# P-MT3620RDB-1-0_PMU.net
KiCad netlist of a schematic drawn in Altium Designer
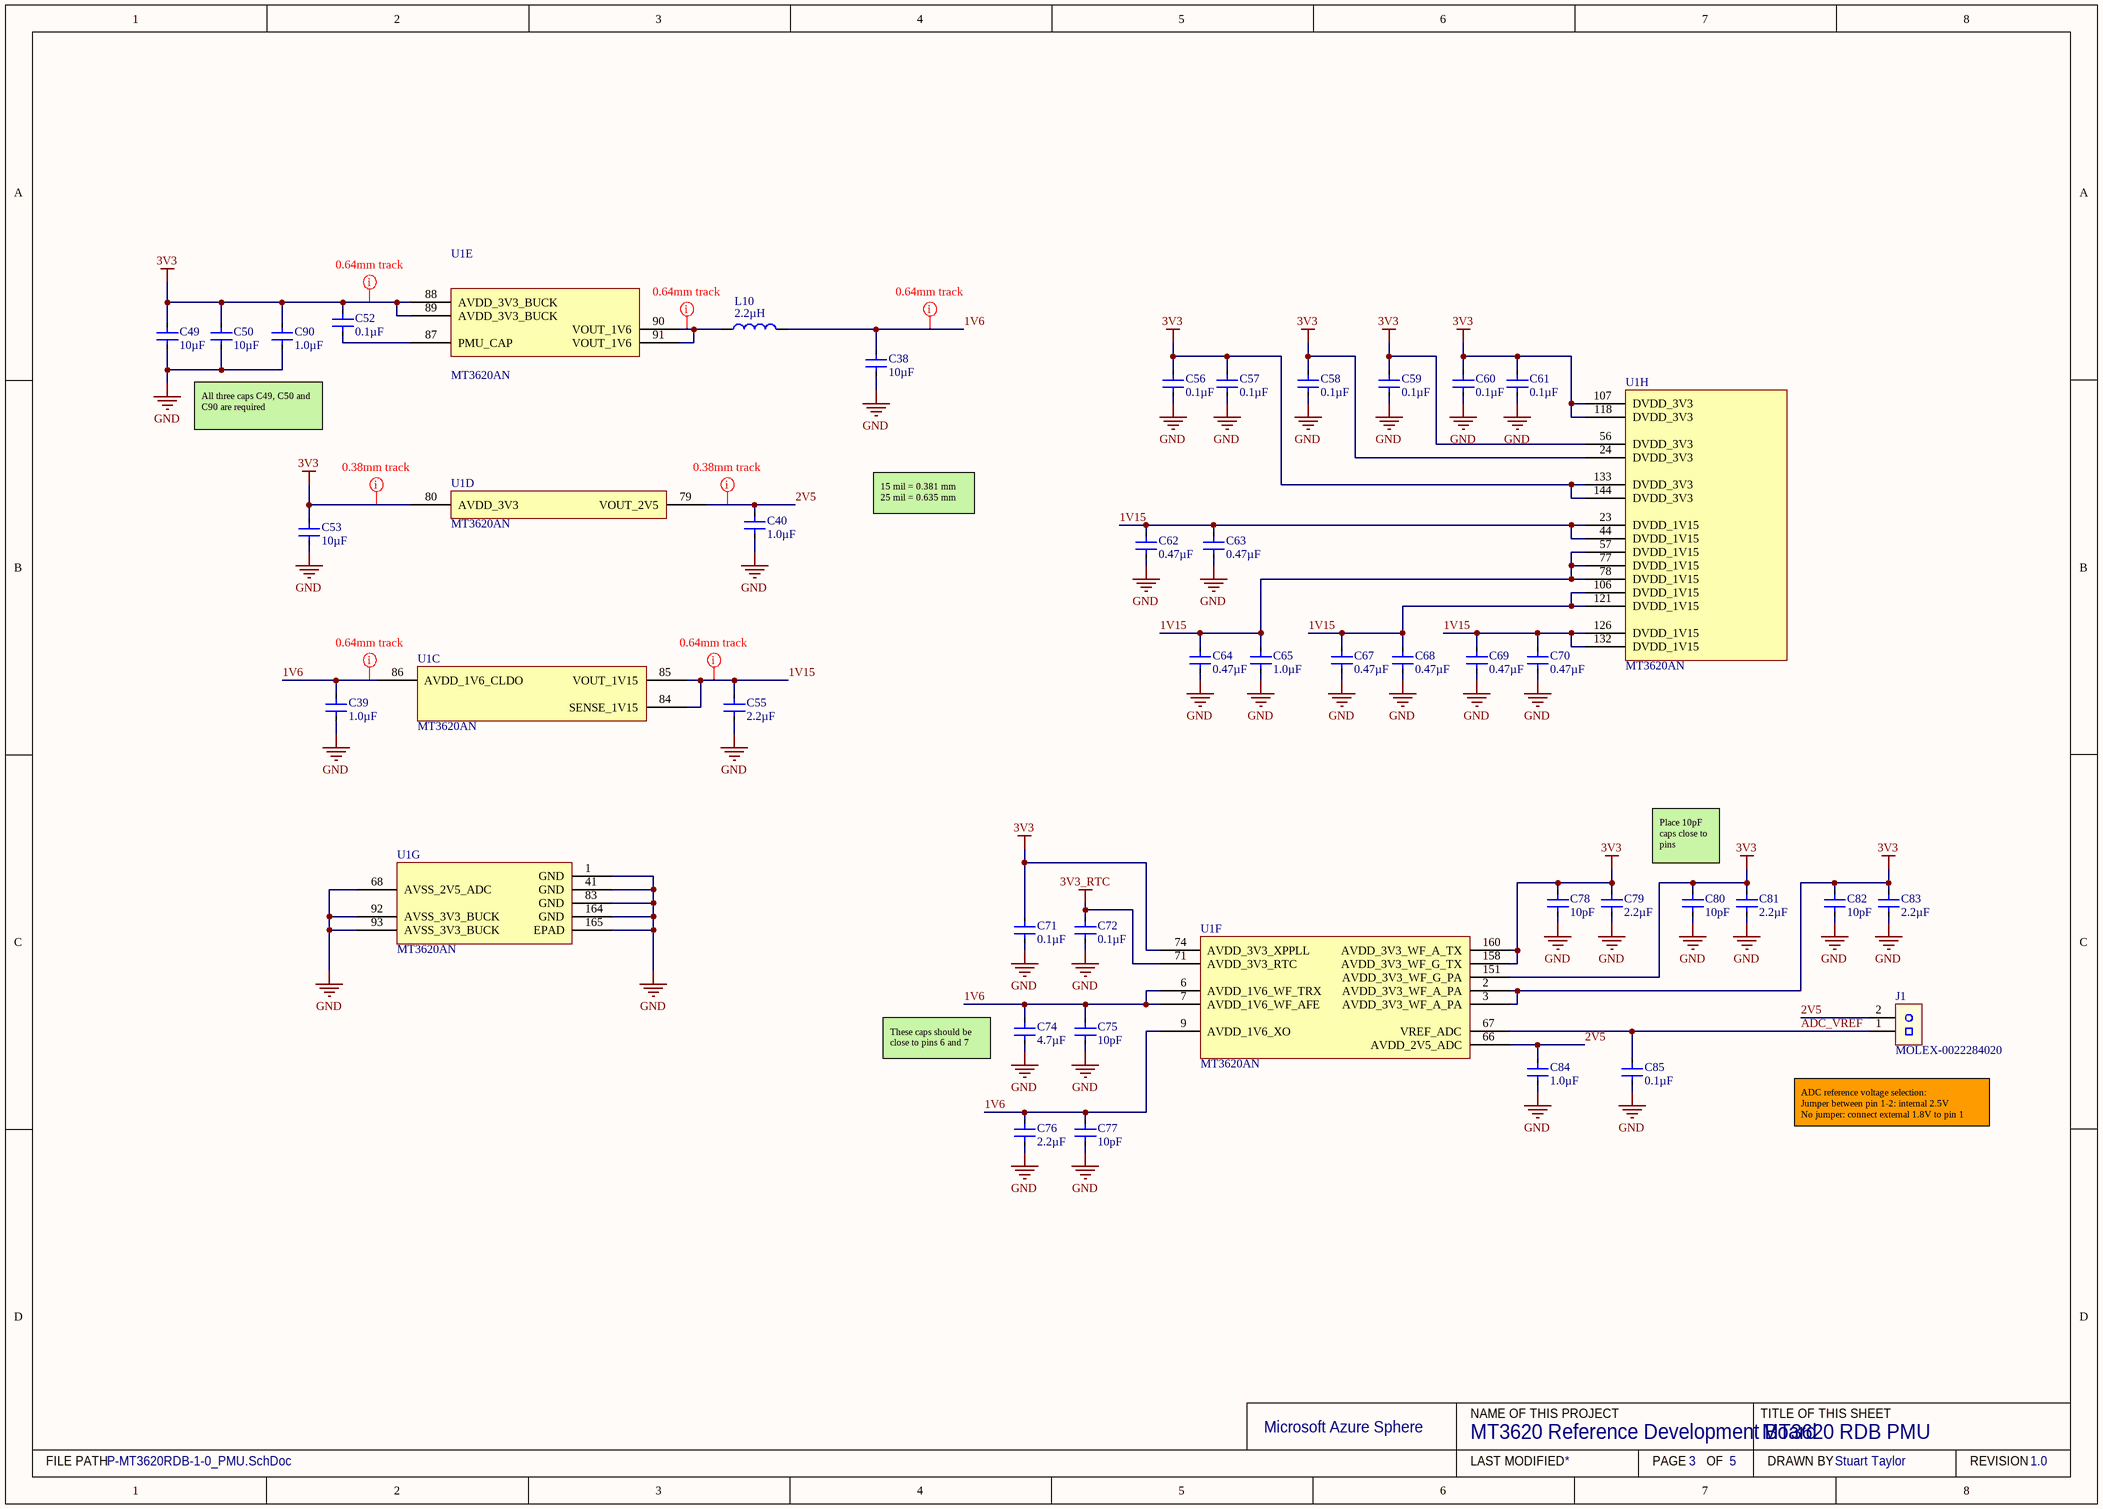
[diagram p0: P-MT3620RDB-1-0_PMU.SchDoc]

(export (version "E")
  (design (tool "Eeschema 10.0.6"))
  (components
    (comp (ref "C38")
      (value "10µF")
      (footprint "CAPC1608-EIA0603-1MM-MED")
      (description "CAP CER 10UF 25V 20% X5R 0603")
      (fields
        (field (name "MANUFACTURER") "TDK Corporation")
        (field (name "MANUFACTURER PART NUMBER") "C1608X5R1E106M080AC")
        (field (name "CAPACITANCE") "10µF")
      )
      (libsource (lib "TDK-Capacitor_C_0603") (part "10µF 0603 X5R 25V"))
    )
    (comp (ref "C39")
      (value "1.0µF")
      (footprint "CAPC1005-EIA0402 0.55MM MED")
      (description "CAP CER 1UF 35V 10% X5R 0402")
      (fields
        (field (name "MANUFACTURER") "TDK Corporation")
        (field (name "MANUFACTURER PART NUMBER") "C1005X5R1V105K050BC")
        (field (name "CAPACITANCE") "1.0µF")
      )
      (libsource (lib "TDK_Capacitor_C_0402") (part "1.0µF 0402 X5R 35V"))
    )
    (comp (ref "C40")
      (value "1.0µF")
      (footprint "CAPC1005-EIA0402 0.55MM MED")
      (description "CAP CER 1UF 35V 10% X5R 0402")
      (fields
        (field (name "MANUFACTURER") "TDK Corporation")
        (field (name "MANUFACTURER PART NUMBER") "C1005X5R1V105K050BC")
        (field (name "CAPACITANCE") "1.0µF")
      )
      (libsource (lib "TDK_Capacitor_C_0402") (part "1.0µF 0402 X5R 35V"))
    )
    (comp (ref "C49")
      (value "10µF")
      (footprint "CAPC1005-EIA0402 0.55MM MED")
      (description "CAP CER 10UF 6.3V 20% X5R 0402")
      (fields
        (field (name "MANUFACTURER") "TDK Corporation")
        (field (name "MANUFACTURER PART NUMBER") "C1005X5R0J106M050BC")
        (field (name "CAPACITANCE") "10µF")
      )
      (libsource (lib "TDK_Capacitor_C_0402") (part "10µF 0402 X5R 6.3V"))
    )
    (comp (ref "C50")
      (value "10µF")
      (footprint "CAPC1005-EIA0402 0.55MM MED")
      (description "CAP CER 10UF 6.3V 20% X5R 0402")
      (fields
        (field (name "MANUFACTURER") "TDK Corporation")
        (field (name "MANUFACTURER PART NUMBER") "C1005X5R0J106M050BC")
        (field (name "CAPACITANCE") "10µF")
      )
      (libsource (lib "TDK_Capacitor_C_0402") (part "10µF 0402 X5R 6.3V"))
    )
    (comp (ref "C52")
      (value "0.1µF")
      (footprint "CAPC1005-EIA0402 0.55MM MED")
      (description "CAP CER 0.1UF 50V 10% X7R 0402")
      (fields
        (field (name "MANUFACTURER") "TDK Corporation")
        (field (name "MANUFACTURER PART NUMBER") "C1005X7R1H104K050BB")
        (field (name "CAPACITANCE") "0.1µF")
      )
      (libsource (lib "TDK_Capacitor_C_0402") (part "0.1µF 0402 X7R 50V"))
    )
    (comp (ref "C53")
      (value "10µF")
      (footprint "CAPC1005-EIA0402 0.55MM MED")
      (description "CAP CER 10UF 6.3V 20% X5R 0402")
      (fields
        (field (name "MANUFACTURER") "TDK Corporation")
        (field (name "MANUFACTURER PART NUMBER") "C1005X5R0J106M050BC")
        (field (name "CAPACITANCE") "10µF")
      )
      (libsource (lib "TDK_Capacitor_C_0402") (part "10µF 0402 X5R 6.3V"))
    )
    (comp (ref "C55")
      (value "2.2µF")
      (footprint "CAPC1005-EIA0402 0.55MM MED")
      (description "CAP CER 2.2UF 35V 10% X5R 0402")
      (fields
        (field (name "MANUFACTURER") "TDK Corporation")
        (field (name "MANUFACTURER PART NUMBER") "C1005X5R1V225K050BC")
        (field (name "CAPACITANCE") "2.2µF")
      )
      (libsource (lib "TDK_Capacitor_C_0402") (part "2.2µF 0402 X5R 35V"))
    )
    (comp (ref "C56")
      (value "0.1µF")
      (footprint "CAPC1005-EIA0402 0.55MM MED")
      (description "CAP CER 0.1UF 50V 10% X7R 0402")
      (fields
        (field (name "MANUFACTURER") "TDK Corporation")
        (field (name "MANUFACTURER PART NUMBER") "C1005X7R1H104K050BB")
        (field (name "CAPACITANCE") "0.1µF")
      )
      (libsource (lib "TDK_Capacitor_C_0402") (part "0.1µF 0402 X7R 50V"))
    )
    (comp (ref "C57")
      (value "0.1µF")
      (footprint "CAPC1005-EIA0402 0.55MM MED")
      (description "CAP CER 0.1UF 50V 10% X7R 0402")
      (fields
        (field (name "MANUFACTURER") "TDK Corporation")
        (field (name "MANUFACTURER PART NUMBER") "C1005X7R1H104K050BB")
        (field (name "CAPACITANCE") "0.1µF")
      )
      (libsource (lib "TDK_Capacitor_C_0402") (part "0.1µF 0402 X7R 50V"))
    )
    (comp (ref "C58")
      (value "0.1µF")
      (footprint "CAPC1005-EIA0402 0.55MM MED")
      (description "CAP CER 0.1UF 50V 10% X7R 0402")
      (fields
        (field (name "MANUFACTURER") "TDK Corporation")
        (field (name "MANUFACTURER PART NUMBER") "C1005X7R1H104K050BB")
        (field (name "CAPACITANCE") "0.1µF")
      )
      (libsource (lib "TDK_Capacitor_C_0402") (part "0.1µF 0402 X7R 50V"))
    )
    (comp (ref "C59")
      (value "0.1µF")
      (footprint "CAPC1005-EIA0402 0.55MM MED")
      (description "CAP CER 0.1UF 50V 10% X7R 0402")
      (fields
        (field (name "MANUFACTURER") "TDK Corporation")
        (field (name "MANUFACTURER PART NUMBER") "C1005X7R1H104K050BB")
        (field (name "CAPACITANCE") "0.1µF")
      )
      (libsource (lib "TDK_Capacitor_C_0402") (part "0.1µF 0402 X7R 50V"))
    )
    (comp (ref "C60")
      (value "0.1µF")
      (footprint "CAPC1005-EIA0402 0.55MM MED")
      (description "CAP CER 0.1UF 50V 10% X7R 0402")
      (fields
        (field (name "MANUFACTURER") "TDK Corporation")
        (field (name "MANUFACTURER PART NUMBER") "C1005X7R1H104K050BB")
        (field (name "CAPACITANCE") "0.1µF")
      )
      (libsource (lib "TDK_Capacitor_C_0402") (part "0.1µF 0402 X7R 50V"))
    )
    (comp (ref "C61")
      (value "0.1µF")
      (footprint "CAPC1005-EIA0402 0.55MM MED")
      (description "CAP CER 0.1UF 50V 10% X7R 0402")
      (fields
        (field (name "MANUFACTURER") "TDK Corporation")
        (field (name "MANUFACTURER PART NUMBER") "C1005X7R1H104K050BB")
        (field (name "CAPACITANCE") "0.1µF")
      )
      (libsource (lib "TDK_Capacitor_C_0402") (part "0.1µF 0402 X7R 50V"))
    )
    (comp (ref "C62")
      (value "0.47µF")
      (footprint "CAPC1005-EIA0402 0.55MM MED")
      (description "CAP CER 0.47UF 35V 10% X5R 0402")
      (fields
        (field (name "MANUFACTURER") "TDK Corporation")
        (field (name "MANUFACTURER PART NUMBER") "C1005X5R1V474K050BC")
        (field (name "CAPACITANCE") "0.47µF")
      )
      (libsource (lib "TDK_Capacitor_C_0402") (part "0.47µF 0402 X5R 35V"))
    )
    (comp (ref "C63")
      (value "0.47µF")
      (footprint "CAPC1005-EIA0402 0.55MM MED")
      (description "CAP CER 0.47UF 35V 10% X5R 0402")
      (fields
        (field (name "MANUFACTURER") "TDK Corporation")
        (field (name "MANUFACTURER PART NUMBER") "C1005X5R1V474K050BC")
        (field (name "CAPACITANCE") "0.47µF")
      )
      (libsource (lib "TDK_Capacitor_C_0402") (part "0.47µF 0402 X5R 35V"))
    )
    (comp (ref "C64")
      (value "0.47µF")
      (footprint "CAPC1005-EIA0402 0.55MM MED")
      (description "CAP CER 0.47UF 35V 10% X5R 0402")
      (fields
        (field (name "MANUFACTURER") "TDK Corporation")
        (field (name "MANUFACTURER PART NUMBER") "C1005X5R1V474K050BC")
        (field (name "CAPACITANCE") "0.47µF")
      )
      (libsource (lib "TDK_Capacitor_C_0402") (part "0.47µF 0402 X5R 35V"))
    )
    (comp (ref "C65")
      (value "1.0µF")
      (footprint "CAPC1005-EIA0402 0.55MM MED")
      (description "CAP CER 1UF 35V 10% X5R 0402")
      (fields
        (field (name "MANUFACTURER") "TDK Corporation")
        (field (name "MANUFACTURER PART NUMBER") "C1005X5R1V105K050BC")
        (field (name "CAPACITANCE") "1.0µF")
      )
      (libsource (lib "TDK_Capacitor_C_0402") (part "1.0µF 0402 X5R 35V"))
    )
    (comp (ref "C67")
      (value "0.47µF")
      (footprint "CAPC1005-EIA0402 0.55MM MED")
      (description "CAP CER 0.47UF 35V 10% X5R 0402")
      (fields
        (field (name "MANUFACTURER") "TDK Corporation")
        (field (name "MANUFACTURER PART NUMBER") "C1005X5R1V474K050BC")
        (field (name "CAPACITANCE") "0.47µF")
      )
      (libsource (lib "TDK_Capacitor_C_0402") (part "0.47µF 0402 X5R 35V"))
    )
    (comp (ref "C68")
      (value "0.47µF")
      (footprint "CAPC1005-EIA0402 0.55MM MED")
      (description "CAP CER 0.47UF 35V 10% X5R 0402")
      (fields
        (field (name "MANUFACTURER") "TDK Corporation")
        (field (name "MANUFACTURER PART NUMBER") "C1005X5R1V474K050BC")
        (field (name "CAPACITANCE") "0.47µF")
      )
      (libsource (lib "TDK_Capacitor_C_0402") (part "0.47µF 0402 X5R 35V"))
    )
    (comp (ref "C69")
      (value "0.47µF")
      (footprint "CAPC1005-EIA0402 0.55MM MED")
      (description "CAP CER 0.47UF 35V 10% X5R 0402")
      (fields
        (field (name "MANUFACTURER") "TDK Corporation")
        (field (name "MANUFACTURER PART NUMBER") "C1005X5R1V474K050BC")
        (field (name "CAPACITANCE") "0.47µF")
      )
      (libsource (lib "TDK_Capacitor_C_0402") (part "0.47µF 0402 X5R 35V"))
    )
    (comp (ref "C70")
      (value "0.47µF")
      (footprint "CAPC1005-EIA0402 0.55MM MED")
      (description "CAP CER 0.47UF 35V 10% X5R 0402")
      (fields
        (field (name "MANUFACTURER") "TDK Corporation")
        (field (name "MANUFACTURER PART NUMBER") "C1005X5R1V474K050BC")
        (field (name "CAPACITANCE") "0.47µF")
      )
      (libsource (lib "TDK_Capacitor_C_0402") (part "0.47µF 0402 X5R 35V"))
    )
    (comp (ref "C71")
      (value "0.1µF")
      (footprint "CAPC1005-EIA0402 0.55MM MED")
      (description "CAP CER 0.1UF 50V 10% X7R 0402")
      (fields
        (field (name "MANUFACTURER") "TDK Corporation")
        (field (name "MANUFACTURER PART NUMBER") "C1005X7R1H104K050BB")
        (field (name "CAPACITANCE") "0.1µF")
      )
      (libsource (lib "TDK_Capacitor_C_0402") (part "0.1µF 0402 X7R 50V"))
    )
    (comp (ref "C72")
      (value "0.1µF")
      (footprint "CAPC1005-EIA0402 0.55MM MED")
      (description "CAP CER 0.1UF 50V 10% X7R 0402")
      (fields
        (field (name "MANUFACTURER") "TDK Corporation")
        (field (name "MANUFACTURER PART NUMBER") "C1005X7R1H104K050BB")
        (field (name "CAPACITANCE") "0.1µF")
      )
      (libsource (lib "TDK_Capacitor_C_0402") (part "0.1µF 0402 X7R 50V"))
    )
    (comp (ref "C74")
      (value "4.7µF")
      (footprint "CAPC1005-EIA0402 0.55MM MED")
      (description "CAP CER 4.7UF 10V 10% X5R 0402")
      (fields
        (field (name "MANUFACTURER") "TDK Corporation")
        (field (name "MANUFACTURER PART NUMBER") "C1005X5R1A475K050BC")
        (field (name "CAPACITANCE") "4.7µF")
      )
      (libsource (lib "TDK_Capacitor_C_0402") (part "4.7µF 0402 X5R 10V"))
    )
    (comp (ref "C75")
      (value "10pF")
      (footprint "CAPC1005-EIA0402 0.55MM MED")
      (description "CAP CER 10PF 50V NP0 0402")
      (fields
        (field (name "MANUFACTURER") "TDK Corporation")
        (field (name "MANUFACTURER PART NUMBER") "C1005C0G1H100D050BA")
        (field (name "CAPACITANCE") "10pF")
      )
      (libsource (lib "TDK_Capacitor_C_0402") (part "10pF 0402 C0G, NP0 50V"))
    )
    (comp (ref "C76")
      (value "2.2µF")
      (footprint "CAPC1005-EIA0402 0.55MM MED")
      (description "CAP CER 2.2UF 35V 10% X5R 0402")
      (fields
        (field (name "MANUFACTURER") "TDK Corporation")
        (field (name "MANUFACTURER PART NUMBER") "C1005X5R1V225K050BC")
        (field (name "CAPACITANCE") "2.2µF")
      )
      (libsource (lib "TDK_Capacitor_C_0402") (part "2.2µF 0402 X5R 35V"))
    )
    (comp (ref "C77")
      (value "10pF")
      (footprint "CAPC1005-EIA0402 0.55MM MED")
      (description "CAP CER 10PF 50V NP0 0402")
      (fields
        (field (name "MANUFACTURER") "TDK Corporation")
        (field (name "MANUFACTURER PART NUMBER") "C1005C0G1H100D050BA")
        (field (name "CAPACITANCE") "10pF")
      )
      (libsource (lib "TDK_Capacitor_C_0402") (part "10pF 0402 C0G, NP0 50V"))
    )
    (comp (ref "C78")
      (value "10pF")
      (footprint "CAPC1005-EIA0402 0.55MM MED")
      (description "CAP CER 10PF 50V NP0 0402")
      (fields
        (field (name "MANUFACTURER") "TDK Corporation")
        (field (name "MANUFACTURER PART NUMBER") "C1005C0G1H100D050BA")
        (field (name "CAPACITANCE") "10pF")
      )
      (libsource (lib "TDK_Capacitor_C_0402") (part "10pF 0402 C0G, NP0 50V"))
    )
    (comp (ref "C79")
      (value "2.2µF")
      (footprint "CAPC1005-EIA0402 0.55MM MED")
      (description "CAP CER 2.2UF 35V 10% X5R 0402")
      (fields
        (field (name "MANUFACTURER") "TDK Corporation")
        (field (name "MANUFACTURER PART NUMBER") "C1005X5R1V225K050BC")
        (field (name "CAPACITANCE") "2.2µF")
      )
      (libsource (lib "TDK_Capacitor_C_0402") (part "2.2µF 0402 X5R 35V"))
    )
    (comp (ref "C80")
      (value "10pF")
      (footprint "CAPC1005-EIA0402 0.55MM MED")
      (description "CAP CER 10PF 50V NP0 0402")
      (fields
        (field (name "MANUFACTURER") "TDK Corporation")
        (field (name "MANUFACTURER PART NUMBER") "C1005C0G1H100D050BA")
        (field (name "CAPACITANCE") "10pF")
      )
      (libsource (lib "TDK_Capacitor_C_0402") (part "10pF 0402 C0G, NP0 50V"))
    )
    (comp (ref "C81")
      (value "2.2µF")
      (footprint "CAPC1005-EIA0402 0.55MM MED")
      (description "CAP CER 2.2UF 35V 10% X5R 0402")
      (fields
        (field (name "MANUFACTURER") "TDK Corporation")
        (field (name "MANUFACTURER PART NUMBER") "C1005X5R1V225K050BC")
        (field (name "CAPACITANCE") "2.2µF")
      )
      (libsource (lib "TDK_Capacitor_C_0402") (part "2.2µF 0402 X5R 35V"))
    )
    (comp (ref "C82")
      (value "10pF")
      (footprint "CAPC1005-EIA0402 0.55MM MED")
      (description "CAP CER 10PF 50V NP0 0402")
      (fields
        (field (name "MANUFACTURER") "TDK Corporation")
        (field (name "MANUFACTURER PART NUMBER") "C1005C0G1H100D050BA")
        (field (name "CAPACITANCE") "10pF")
      )
      (libsource (lib "TDK_Capacitor_C_0402") (part "10pF 0402 C0G, NP0 50V"))
    )
    (comp (ref "C83")
      (value "2.2µF")
      (footprint "CAPC1005-EIA0402 0.55MM MED")
      (description "CAP CER 2.2UF 35V 10% X5R 0402")
      (fields
        (field (name "MANUFACTURER") "TDK Corporation")
        (field (name "MANUFACTURER PART NUMBER") "C1005X5R1V225K050BC")
        (field (name "CAPACITANCE") "2.2µF")
      )
      (libsource (lib "TDK_Capacitor_C_0402") (part "2.2µF 0402 X5R 35V"))
    )
    (comp (ref "C84")
      (value "1.0µF")
      (footprint "CAPC1005-EIA0402 0.55MM MED")
      (description "CAP CER 1UF 35V 10% X5R 0402")
      (fields
        (field (name "MANUFACTURER") "TDK Corporation")
        (field (name "MANUFACTURER PART NUMBER") "C1005X5R1V105K050BC")
        (field (name "CAPACITANCE") "1.0µF")
      )
      (libsource (lib "TDK_Capacitor_C_0402") (part "1.0µF 0402 X5R 35V"))
    )
    (comp (ref "C85")
      (value "0.1µF")
      (footprint "CAPC1005-EIA0402 0.55MM MED")
      (description "CAP CER 0.1UF 50V 10% X7R 0402")
      (fields
        (field (name "MANUFACTURER") "TDK Corporation")
        (field (name "MANUFACTURER PART NUMBER") "C1005X7R1H104K050BB")
        (field (name "CAPACITANCE") "0.1µF")
      )
      (libsource (lib "TDK_Capacitor_C_0402") (part "0.1µF 0402 X7R 50V"))
    )
    (comp (ref "C90")
      (value "1.0µF")
      (footprint "CAPC1005-EIA0402 0.55MM MED")
      (description "CAP CER 1UF 35V 10% X5R 0402")
      (fields
        (field (name "MANUFACTURER") "TDK Corporation")
        (field (name "MANUFACTURER PART NUMBER") "C1005X5R1V105K050BC")
        (field (name "CAPACITANCE") "1.0µF")
      )
      (libsource (lib "TDK_Capacitor_C_0402") (part "1.0µF 0402 X5R 35V"))
    )
    (comp (ref "J1")
      (value "MOLEX-0022284020")
      (footprint "0022284020")
      (description "CONN HEADER 2POS .100 VERT TIN")
      (fields
        (field (name "MANUFACTURER") "Molex, LLC")
        (field (name "MANUFACTURER PART NUMBER") "0022284020")
      )
      (libsource (lib "Molex") (part "MOLEX-0022284020"))
    )
    (comp (ref "L10")
      (value "2.2µH")
      (footprint "MAMK2520T2R2M")
      (description "FIXED IND 2.2UH 1.9A 117 MOHM")
      (fields
        (field (name "MANUFACTURER") "Taiyo Yuden")
        (field (name "MANUFACTURER PART NUMBER") "MAMK2520T2R2M")
      )
      (libsource (lib "TaiyoYuden ") (part "MAMK2520T2R2M"))
    )
    (comp (ref "U1")
      (value "MT3620AN")
      (footprint "MT3620_MaskSquaresVias50")
      (fields (field (name "MANUFACTURER") "MediaTek Inc."))
      (libsource (lib "Microsoft") (part "MT3620AN"))
    )
  )
  (nets
    (net (code "1") (name "/1V6") (class "Default")
      (node (ref "C38") (pin "2") (pinfunction "2_2") (pintype "passive"))
      (node (ref "C39") (pin "2") (pinfunction "2_2") (pintype "passive"))
      (node (ref "C74") (pin "2") (pinfunction "2_2") (pintype "passive"))
      (node (ref "C75") (pin "2") (pinfunction "2_2") (pintype "passive"))
      (node (ref "C76") (pin "2") (pinfunction "2_2") (pintype "passive"))
      (node (ref "C77") (pin "2") (pinfunction "2_2") (pintype "passive"))
      (node (ref "L10") (pin "2") (pinfunction "2_2") (pintype "passive"))
      (node (ref "U1") (pin "6") (pinfunction "AVDD_1V6_WF_TRX_6") (pintype "passive"))
      (node (ref "U1") (pin "7") (pinfunction "AVDD_1V6_WF_AFE_7") (pintype "passive"))
      (node (ref "U1") (pin "86") (pinfunction "AVDD_1V6_CLDO_86") (pintype "passive"))
      (node (ref "U1") (pin "9") (pinfunction "AVDD_1V6_XO_9") (pintype "passive"))
    )
    (net (code "2") (name "/1V15") (class "Default")
      (node (ref "C55") (pin "2") (pinfunction "2_2") (pintype "passive"))
      (node (ref "C62") (pin "2") (pinfunction "2_2") (pintype "passive"))
      (node (ref "C63") (pin "2") (pinfunction "2_2") (pintype "passive"))
      (node (ref "C64") (pin "2") (pinfunction "2_2") (pintype "passive"))
      (node (ref "C65") (pin "2") (pinfunction "2_2") (pintype "passive"))
      (node (ref "C67") (pin "2") (pinfunction "2_2") (pintype "passive"))
      (node (ref "C68") (pin "2") (pinfunction "2_2") (pintype "passive"))
      (node (ref "C69") (pin "2") (pinfunction "2_2") (pintype "passive"))
      (node (ref "C70") (pin "2") (pinfunction "2_2") (pintype "passive"))
      (node (ref "U1") (pin "106") (pinfunction "DVDD_1V15_106") (pintype "passive"))
      (node (ref "U1") (pin "121") (pinfunction "DVDD_1V15_121") (pintype "passive"))
      (node (ref "U1") (pin "126") (pinfunction "DVDD_1V15_126") (pintype "passive"))
      (node (ref "U1") (pin "132") (pinfunction "DVDD_1V15_132") (pintype "passive"))
      (node (ref "U1") (pin "23") (pinfunction "DVDD_1V15_23") (pintype "passive"))
      (node (ref "U1") (pin "44") (pinfunction "DVDD_1V15_44") (pintype "passive"))
      (node (ref "U1") (pin "57") (pinfunction "DVDD_1V15_57") (pintype "passive"))
      (node (ref "U1") (pin "77") (pinfunction "DVDD_1V15_77") (pintype "passive"))
      (node (ref "U1") (pin "78") (pinfunction "DVDD_1V15_78") (pintype "passive"))
      (node (ref "U1") (pin "84") (pinfunction "SENSE_1V15_84") (pintype "passive"))
      (node (ref "U1") (pin "85") (pinfunction "VOUT_1V15_85") (pintype "passive"))
    )
    (net (code "3") (name "/2V5") (class "Default")
      (node (ref "C40") (pin "2") (pinfunction "2_2") (pintype "passive"))
      (node (ref "C84") (pin "2") (pinfunction "2_2") (pintype "passive"))
      (node (ref "J1") (pin "2") (pinfunction "2_2") (pintype "passive"))
      (node (ref "U1") (pin "66") (pinfunction "AVDD_2V5_ADC_66") (pintype "passive"))
      (node (ref "U1") (pin "79") (pinfunction "VOUT_2V5_79") (pintype "passive"))
    )
    (net (code "4") (name "/ADC_VREF") (class "Default")
      (node (ref "C85") (pin "2") (pinfunction "2_2") (pintype "passive"))
      (node (ref "J1") (pin "1") (pinfunction "1_1") (pintype "passive"))
      (node (ref "U1") (pin "67") (pinfunction "VREF_ADC_67") (pintype "passive"))
    )
    (net (code "5") (name "3V3") (class "Default")
      (node (ref "C49") (pin "2") (pinfunction "2_2") (pintype "passive"))
      (node (ref "C50") (pin "2") (pinfunction "2_2") (pintype "passive"))
      (node (ref "C52") (pin "2") (pinfunction "2_2") (pintype "passive"))
      (node (ref "C53") (pin "2") (pinfunction "2_2") (pintype "passive"))
      (node (ref "C56") (pin "2") (pinfunction "2_2") (pintype "passive"))
      (node (ref "C57") (pin "2") (pinfunction "2_2") (pintype "passive"))
      (node (ref "C58") (pin "2") (pinfunction "2_2") (pintype "passive"))
      (node (ref "C59") (pin "2") (pinfunction "2_2") (pintype "passive"))
      (node (ref "C60") (pin "2") (pinfunction "2_2") (pintype "passive"))
      (node (ref "C61") (pin "2") (pinfunction "2_2") (pintype "passive"))
      (node (ref "C71") (pin "2") (pinfunction "2_2") (pintype "passive"))
      (node (ref "C78") (pin "2") (pinfunction "2_2") (pintype "passive"))
      (node (ref "C79") (pin "2") (pinfunction "2_2") (pintype "passive"))
      (node (ref "C80") (pin "2") (pinfunction "2_2") (pintype "passive"))
      (node (ref "C81") (pin "2") (pinfunction "2_2") (pintype "passive"))
      (node (ref "C82") (pin "2") (pinfunction "2_2") (pintype "passive"))
      (node (ref "C83") (pin "2") (pinfunction "2_2") (pintype "passive"))
      (node (ref "C90") (pin "2") (pinfunction "2_2") (pintype "passive"))
      (node (ref "U1") (pin "107") (pinfunction "DVDD_3V3_107") (pintype "passive"))
      (node (ref "U1") (pin "118") (pinfunction "DVDD_3V3_118") (pintype "passive"))
      (node (ref "U1") (pin "133") (pinfunction "DVDD_3V3_133") (pintype "passive"))
      (node (ref "U1") (pin "144") (pinfunction "DVDD_3V3_144") (pintype "passive"))
      (node (ref "U1") (pin "151") (pinfunction "AVDD_3V3_WF_G_PA_151") (pintype "passive"))
      (node (ref "U1") (pin "158") (pinfunction "AVDD_3V3_WF_G_TX_158") (pintype "passive"))
      (node (ref "U1") (pin "160") (pinfunction "AVDD_3V3_WF_A_TX_160") (pintype "passive"))
      (node (ref "U1") (pin "2") (pinfunction "AVDD_3V3_WF_A_PA_2") (pintype "passive"))
      (node (ref "U1") (pin "24") (pinfunction "DVDD_3V3_24") (pintype "passive"))
      (node (ref "U1") (pin "3") (pinfunction "AVDD_3V3_WF_A_PA_3") (pintype "passive"))
      (node (ref "U1") (pin "56") (pinfunction "DVDD_3V3_56") (pintype "passive"))
      (node (ref "U1") (pin "74") (pinfunction "AVDD_3V3_XPPLL_74") (pintype "passive"))
      (node (ref "U1") (pin "80") (pinfunction "AVDD_3V3_80") (pintype "passive"))
      (node (ref "U1") (pin "88") (pinfunction "AVDD_3V3_BUCK_88") (pintype "passive"))
      (node (ref "U1") (pin "89") (pinfunction "AVDD_3V3_BUCK_89") (pintype "passive"))
    )
    (net (code "6") (name "3V3_RTC") (class "Default")
      (node (ref "C72") (pin "2") (pinfunction "2_2") (pintype "passive"))
      (node (ref "U1") (pin "71") (pinfunction "AVDD_3V3_RTC_71") (pintype "passive"))
    )
    (net (code "7") (name "GND") (class "Default")
      (node (ref "C38") (pin "1") (pinfunction "1_1") (pintype "passive"))
      (node (ref "C39") (pin "1") (pinfunction "1_1") (pintype "passive"))
      (node (ref "C40") (pin "1") (pinfunction "1_1") (pintype "passive"))
      (node (ref "C49") (pin "1") (pinfunction "1_1") (pintype "passive"))
      (node (ref "C50") (pin "1") (pinfunction "1_1") (pintype "passive"))
      (node (ref "C53") (pin "1") (pinfunction "1_1") (pintype "passive"))
      (node (ref "C55") (pin "1") (pinfunction "1_1") (pintype "passive"))
      (node (ref "C56") (pin "1") (pinfunction "1_1") (pintype "passive"))
      (node (ref "C57") (pin "1") (pinfunction "1_1") (pintype "passive"))
      (node (ref "C58") (pin "1") (pinfunction "1_1") (pintype "passive"))
      (node (ref "C59") (pin "1") (pinfunction "1_1") (pintype "passive"))
      (node (ref "C60") (pin "1") (pinfunction "1_1") (pintype "passive"))
      (node (ref "C61") (pin "1") (pinfunction "1_1") (pintype "passive"))
      (node (ref "C62") (pin "1") (pinfunction "1_1") (pintype "passive"))
      (node (ref "C63") (pin "1") (pinfunction "1_1") (pintype "passive"))
      (node (ref "C64") (pin "1") (pinfunction "1_1") (pintype "passive"))
      (node (ref "C65") (pin "1") (pinfunction "1_1") (pintype "passive"))
      (node (ref "C67") (pin "1") (pinfunction "1_1") (pintype "passive"))
      (node (ref "C68") (pin "1") (pinfunction "1_1") (pintype "passive"))
      (node (ref "C69") (pin "1") (pinfunction "1_1") (pintype "passive"))
      (node (ref "C70") (pin "1") (pinfunction "1_1") (pintype "passive"))
      (node (ref "C71") (pin "1") (pinfunction "1_1") (pintype "passive"))
      (node (ref "C72") (pin "1") (pinfunction "1_1") (pintype "passive"))
      (node (ref "C74") (pin "1") (pinfunction "1_1") (pintype "passive"))
      (node (ref "C75") (pin "1") (pinfunction "1_1") (pintype "passive"))
      (node (ref "C76") (pin "1") (pinfunction "1_1") (pintype "passive"))
      (node (ref "C77") (pin "1") (pinfunction "1_1") (pintype "passive"))
      (node (ref "C78") (pin "1") (pinfunction "1_1") (pintype "passive"))
      (node (ref "C79") (pin "1") (pinfunction "1_1") (pintype "passive"))
      (node (ref "C80") (pin "1") (pinfunction "1_1") (pintype "passive"))
      (node (ref "C81") (pin "1") (pinfunction "1_1") (pintype "passive"))
      (node (ref "C82") (pin "1") (pinfunction "1_1") (pintype "passive"))
      (node (ref "C83") (pin "1") (pinfunction "1_1") (pintype "passive"))
      (node (ref "C84") (pin "1") (pinfunction "1_1") (pintype "passive"))
      (node (ref "C85") (pin "1") (pinfunction "1_1") (pintype "passive"))
      (node (ref "C90") (pin "1") (pinfunction "1_1") (pintype "passive"))
      (node (ref "U1") (pin "1") (pinfunction "GND_1") (pintype "passive"))
      (node (ref "U1") (pin "164") (pinfunction "GND_164") (pintype "passive"))
      (node (ref "U1") (pin "165") (pinfunction "EPAD_165") (pintype "passive"))
      (node (ref "U1") (pin "41") (pinfunction "GND_41") (pintype "passive"))
      (node (ref "U1") (pin "68") (pinfunction "AVSS_2V5_ADC_68") (pintype "passive"))
      (node (ref "U1") (pin "83") (pinfunction "GND_83") (pintype "passive"))
      (node (ref "U1") (pin "92") (pinfunction "AVSS_3V3_BUCK_92") (pintype "passive"))
      (node (ref "U1") (pin "93") (pinfunction "AVSS_3V3_BUCK_93") (pintype "passive"))
    )
    (net (code "8") (name "Net-(L10-Pad1)") (class "Default")
      (node (ref "L10") (pin "1") (pinfunction "1_1") (pintype "passive"))
      (node (ref "U1") (pin "90") (pinfunction "VOUT_1V6_90") (pintype "passive"))
      (node (ref "U1") (pin "91") (pinfunction "VOUT_1V6_91") (pintype "passive"))
    )
    (net (code "9") (name "Net-(U1E-PMU_CAP)") (class "Default")
      (node (ref "C52") (pin "1") (pinfunction "1_1") (pintype "passive"))
      (node (ref "U1") (pin "87") (pinfunction "PMU_CAP_87") (pintype "passive"))
    )
  )
)
